# Power.net
KiCad netlist of a schematic drawn in Altium Designer
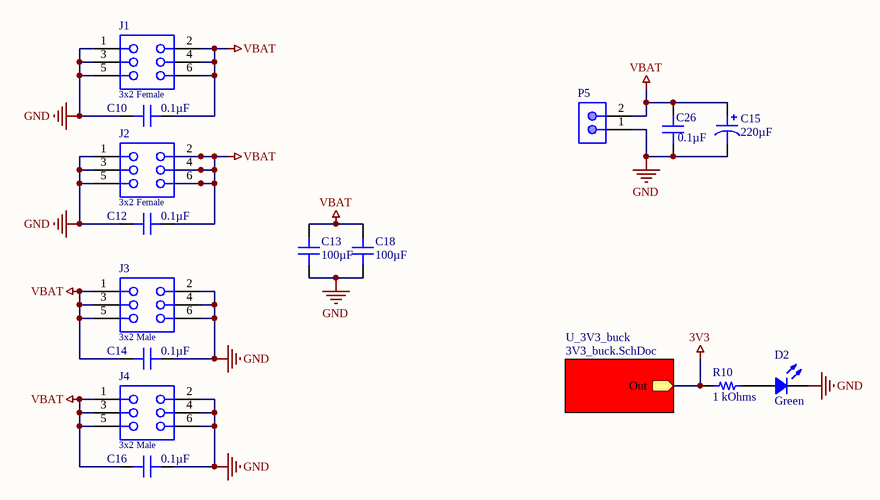
[diagram p0: Power.SchDoc]

(export (version "E")
  (design (tool "Eeschema 10.0.6"))
  (components
    (comp (ref "C10")
      (value "0.1µF")
      (footprint "CAP 0603_1608")
      (description "CAP CER 0.1UF 100V 0603 EPOXY")
      (fields
        (field (name "PART NUMBER") "GCG188R92A104KA03D")
        (field (name "MANUFACTURER") "Murata Electronics")
      )
      (libsource (lib "Celestial Altium Library - altium_library") (part "Capacitor"))
    )
    (comp (ref "C12")
      (value "0.1µF")
      (footprint "CAP 0603_1608")
      (description "CAP CER 0.1UF 100V 0603 EPOXY")
      (fields
        (field (name "PART NUMBER") "GCG188R92A104KA03D")
        (field (name "MANUFACTURER") "Murata Electronics")
      )
      (libsource (lib "Celestial Altium Library - altium_library") (part "Capacitor"))
    )
    (comp (ref "C13")
      (value "100µF")
      (footprint "CAP 1210_3225 - 2.8MM")
      (description "CAP CER 100UF 16V X5R 1210")
      (fields (field (name "PART NUMBER") "EMK325ABJ107MM-P") (field (name "MANUFACTURER") "Taiyo Yuden"))
      (libsource (lib "Celestial Altium Library - altium_library") (part "Capacitor"))
    )
    (comp (ref "C14")
      (value "0.1µF")
      (footprint "CAP 0603_1608")
      (description "CAP CER 0.1UF 100V 0603 EPOXY")
      (fields
        (field (name "PART NUMBER") "GCG188R92A104KA03D")
        (field (name "MANUFACTURER") "Murata Electronics")
      )
      (libsource (lib "Celestial Altium Library - altium_library") (part "Capacitor"))
    )
    (comp (ref "C15")
      (value "220µF")
      (footprint "CAP POL 2917_7343")
      (description "CAP TANT 220UF 10% 16V 2917")
      (fields (field (name "PART NUMBER") "T510X227K016ATE040") (field (name "MANUFACTURER") "KEMET"))
      (libsource (lib "Celestial Altium Library - altium_library") (part "Polarised Capacitor"))
    )
    (comp (ref "C16")
      (value "0.1µF")
      (footprint "CAP 0603_1608")
      (description "CAP CER 0.1UF 100V 0603 EPOXY")
      (fields
        (field (name "PART NUMBER") "GCG188R92A104KA03D")
        (field (name "MANUFACTURER") "Murata Electronics")
      )
      (libsource (lib "Celestial Altium Library - altium_library") (part "Capacitor"))
    )
    (comp (ref "C18")
      (value "100µF")
      (footprint "CAP 1210_3225 - 2.8MM")
      (description "CAP CER 100UF 16V X5R 1210")
      (fields (field (name "PART NUMBER") "EMK325ABJ107MM-P") (field (name "MANUFACTURER") "Taiyo Yuden"))
      (libsource (lib "Celestial Altium Library - altium_library") (part "Capacitor"))
    )
    (comp (ref "C26")
      (value "0.1µF")
      (footprint "CAP 0603_1608")
      (description "CAP CER 0.1UF 100V 0603 EPOXY")
      (fields
        (field (name "PART NUMBER") "GCG188R92A104KA03D")
        (field (name "MANUFACTURER") "Murata Electronics")
      )
      (libsource (lib "Celestial Altium Library - altium_library") (part "Capacitor"))
    )
    (comp (ref "D2")
      (value "Green")
      (footprint "LED 0603_1608 GREEN")
      (description "1.6X0.8MM LC GREEN PIXSOLED DOME")
      (fields (field (name "PART NUMBER") "XZCDGK53W-8VF") (field (name "MANUFACTURER") "SunLED"))
      (libsource (lib "Celestial Altium Library - altium_library") (part "LED"))
    )
    (comp (ref "J1")
      (value "3x2 Female")
      (footprint "62000621821")
      (description "WR-PHD Socket Header, THT, pitch 2mm, Dual Row, Vertical, 6p")
      (fields
        (field (name "MANUFACTURER PART NUMBER") "62000621821")
        (field (name "MANUFACTURER") "Wurth Elektronik")
      )
      (libsource (lib "Altium_WR-PHD") (part "62000621821"))
    )
    (comp (ref "J2")
      (value "3x2 Female")
      (footprint "62000621821")
      (description "WR-PHD Socket Header, THT, pitch 2mm, Dual Row, Vertical, 6p")
      (fields
        (field (name "MANUFACTURER PART NUMBER") "62000621821")
        (field (name "MANUFACTURER") "Wurth Elektronik")
      )
      (libsource (lib "Altium_WR-PHD") (part "62000621821"))
    )
    (comp (ref "J3")
      (value "3x2 Male")
      (footprint "2mm 3x2 Male Right - duplicate")
      (description "2mm Male 3x2 Right")
      (fields
        (field (name "MANUFACTURER PART NUMBER") "62000621821")
        (field (name "MANUFACTURER") "Wurth Elektronik")
      )
      (libsource (lib "IC") (part "2mm Male 3x2 Right"))
    )
    (comp (ref "J4")
      (value "3x2 Male")
      (footprint "2mm 3x2 Male Right - duplicate")
      (description "2mm Male 3x2 Right")
      (fields
        (field (name "MANUFACTURER PART NUMBER") "62000621821")
        (field (name "MANUFACTURER") "Wurth Elektronik")
      )
      (libsource (lib "IC") (part "2mm Male 3x2 Right"))
    )
    (comp (ref "P5")
      (value "2 pin 2mm JST Male")
      (footprint "2pin - 2mm JST male")
      (libsource (lib "IC") (part "2 pin 2mm JST Male"))
    )
    (comp (ref "R10")
      (value "1 kOhms")
      (footprint "RES 0603_1608")
      (description "RES 1K OHM 0.5% 1/10W 0603")
      (fields
        (field (name "PART NUMBER") "RNCF0603DTE1K00")
        (field (name "MANUFACTURER") "Stackpole Electronics Inc")
      )
      (libsource (lib "Celestial Altium Library - altium_library") (part "Resistor"))
    )
  )
  (nets
    (net (code "1") (name "3V3") (class "Default")
      (node (ref "R10") (pin "1") (pinfunction "1_1") (pintype "passive"))
    )
    (net (code "2") (name "GND") (class "Default")
      (node (ref "C10") (pin "1") (pinfunction "1_1") (pintype "passive"))
      (node (ref "C12") (pin "1") (pinfunction "1_1") (pintype "passive"))
      (node (ref "C13") (pin "1") (pinfunction "1_1") (pintype "passive"))
      (node (ref "C14") (pin "2") (pinfunction "2_2") (pintype "passive"))
      (node (ref "C15") (pin "2") (pinfunction "2_2") (pintype "passive"))
      (node (ref "C16") (pin "2") (pinfunction "2_2") (pintype "passive"))
      (node (ref "C18") (pin "1") (pinfunction "1_1") (pintype "passive"))
      (node (ref "C26") (pin "2") (pinfunction "2_2") (pintype "passive"))
      (node (ref "D2") (pin "2") (pinfunction "2_2") (pintype "passive"))
      (node (ref "J1") (pin "1") (pinfunction "1_1") (pintype "passive"))
      (node (ref "J1") (pin "3") (pinfunction "3_3") (pintype "passive"))
      (node (ref "J1") (pin "5") (pinfunction "5_5") (pintype "passive"))
      (node (ref "J2") (pin "1") (pinfunction "1_1") (pintype "passive"))
      (node (ref "J2") (pin "3") (pinfunction "3_3") (pintype "passive"))
      (node (ref "J2") (pin "5") (pinfunction "5_5") (pintype "passive"))
      (node (ref "J3") (pin "2") (pinfunction "2_2") (pintype "passive"))
      (node (ref "J3") (pin "4") (pinfunction "4_4") (pintype "passive"))
      (node (ref "J3") (pin "6") (pinfunction "6_6") (pintype "passive"))
      (node (ref "J4") (pin "2") (pinfunction "2_2") (pintype "passive"))
      (node (ref "J4") (pin "4") (pinfunction "4_4") (pintype "passive"))
      (node (ref "J4") (pin "6") (pinfunction "6_6") (pintype "passive"))
      (node (ref "P5") (pin "1") (pinfunction "1_1") (pintype "passive"))
    )
    (net (code "3") (name "Net-(D2-Pad1)") (class "Default")
      (node (ref "D2") (pin "1") (pinfunction "1_1") (pintype "passive"))
      (node (ref "R10") (pin "2") (pinfunction "2_2") (pintype "passive"))
    )
    (net (code "4") (name "VBAT") (class "Default")
      (node (ref "C10") (pin "2") (pinfunction "2_2") (pintype "passive"))
      (node (ref "C12") (pin "2") (pinfunction "2_2") (pintype "passive"))
      (node (ref "C13") (pin "2") (pinfunction "2_2") (pintype "passive"))
      (node (ref "C14") (pin "1") (pinfunction "1_1") (pintype "passive"))
      (node (ref "C15") (pin "1") (pinfunction "1_1") (pintype "passive"))
      (node (ref "C16") (pin "1") (pinfunction "1_1") (pintype "passive"))
      (node (ref "C18") (pin "2") (pinfunction "2_2") (pintype "passive"))
      (node (ref "C26") (pin "1") (pinfunction "1_1") (pintype "passive"))
      (node (ref "J1") (pin "2") (pinfunction "2_2") (pintype "passive"))
      (node (ref "J1") (pin "4") (pinfunction "4_4") (pintype "passive"))
      (node (ref "J1") (pin "6") (pinfunction "6_6") (pintype "passive"))
      (node (ref "J2") (pin "2") (pinfunction "2_2") (pintype "passive"))
      (node (ref "J2") (pin "4") (pinfunction "4_4") (pintype "passive"))
      (node (ref "J2") (pin "6") (pinfunction "6_6") (pintype "passive"))
      (node (ref "J3") (pin "1") (pinfunction "1_1") (pintype "passive"))
      (node (ref "J3") (pin "3") (pinfunction "3_3") (pintype "passive"))
      (node (ref "J3") (pin "5") (pinfunction "5_5") (pintype "passive"))
      (node (ref "J4") (pin "1") (pinfunction "1_1") (pintype "passive"))
      (node (ref "J4") (pin "3") (pinfunction "3_3") (pintype "passive"))
      (node (ref "J4") (pin "5") (pinfunction "5_5") (pintype "passive"))
      (node (ref "P5") (pin "2") (pinfunction "2_2") (pintype "passive"))
    )
  )
)
